# PCB-SLIDER45.net
KiCad netlist of a schematic drawn in EAGLE
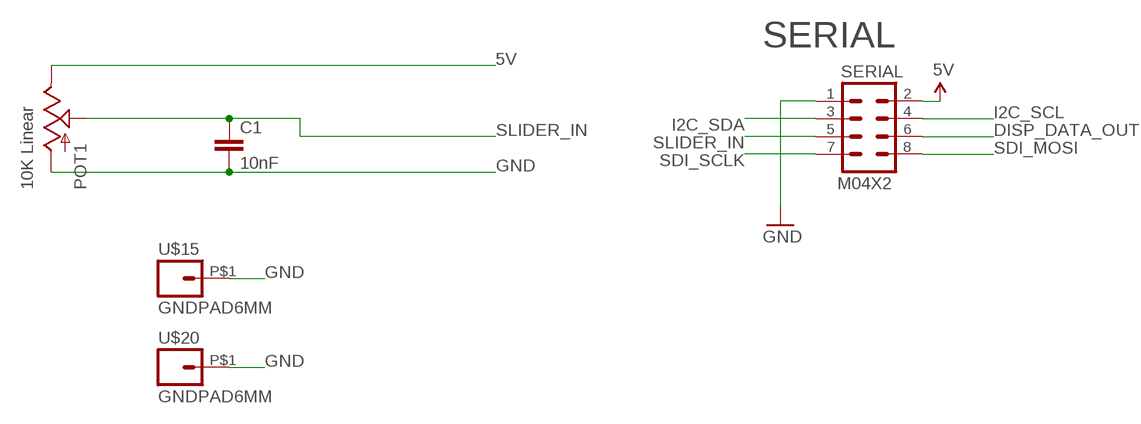
[diagram p0: schematic, sheet 1]

(export (version "E")
  (design (tool "Eeschema 10.0.6"))
  (components
    (comp (ref "C1")
      (value "10nF")
      (footprint "eagle-import:0603-CAP")
      (libsource (lib "eagle-import") (part "CAP0603-CAP"))
    )
    (comp (ref "POT1")
      (value "10K Linear")
      (footprint "eagle-import:SLIDER45")
      (libsource (lib "eagle-import") (part "SLIDER45"))
    )
    (comp (ref "SERIAL")
      (value "M04X2")
      (footprint "eagle-import:2X4")
      (libsource (lib "eagle-import") (part "M04X2"))
    )
    (comp (ref "U$15")
      (value "GNDPAD6MM")
      (footprint "eagle-import:3.2MMPAD6MM")
      (libsource (lib "eagle-import") (part "GNDPAD6MM"))
    )
    (comp (ref "U$20")
      (value "GNDPAD6MM")
      (footprint "eagle-import:3.2MMPAD6MM")
      (libsource (lib "eagle-import") (part "GNDPAD6MM"))
    )
  )
  (nets
    (net (code "1") (name "/DISP_DATA_OUT") (class "Default")
      (node (ref "SERIAL") (pin "6") (pinfunction "6_6") (pintype "passive"))
    )
    (net (code "2") (name "/I2C_SCL") (class "Default")
      (node (ref "SERIAL") (pin "4") (pinfunction "4_4") (pintype "passive"))
    )
    (net (code "3") (name "/I2C_SDA") (class "Default")
      (node (ref "SERIAL") (pin "3") (pinfunction "3_3") (pintype "passive"))
    )
    (net (code "4") (name "/SDI_MOSI") (class "Default")
      (node (ref "SERIAL") (pin "8") (pinfunction "8_8") (pintype "passive"))
    )
    (net (code "5") (name "/SDI_SCLK") (class "Default")
      (node (ref "SERIAL") (pin "7") (pinfunction "7_7") (pintype "passive"))
    )
    (net (code "6") (name "/SLIDER_IN") (class "Default")
      (node (ref "C1") (pin "1") (pinfunction "1_1") (pintype "passive"))
      (node (ref "POT1") (pin "2A") (pinfunction "S_2A") (pintype "passive"))
      (node (ref "SERIAL") (pin "5") (pinfunction "5_5") (pintype "passive"))
    )
    (net (code "7") (name "5V") (class "Default")
      (node (ref "POT1") (pin "1") (pinfunction "E_1") (pintype "passive"))
      (node (ref "SERIAL") (pin "2") (pinfunction "2_2") (pintype "passive"))
    )
    (net (code "8") (name "GND") (class "Default")
      (node (ref "C1") (pin "2") (pinfunction "2_2") (pintype "passive"))
      (node (ref "POT1") (pin "3") (pinfunction "A_3") (pintype "passive"))
      (node (ref "SERIAL") (pin "1") (pinfunction "1_1") (pintype "passive"))
      (node (ref "U$15") (pin "P$1") (pinfunction "1_P$1") (pintype "passive"))
      (node (ref "U$20") (pin "P$1") (pinfunction "1_P$1") (pintype "passive"))
    )
  )
)
